# 3x3_Matrix.net
KiCad netlist of a schematic drawn in EAGLE
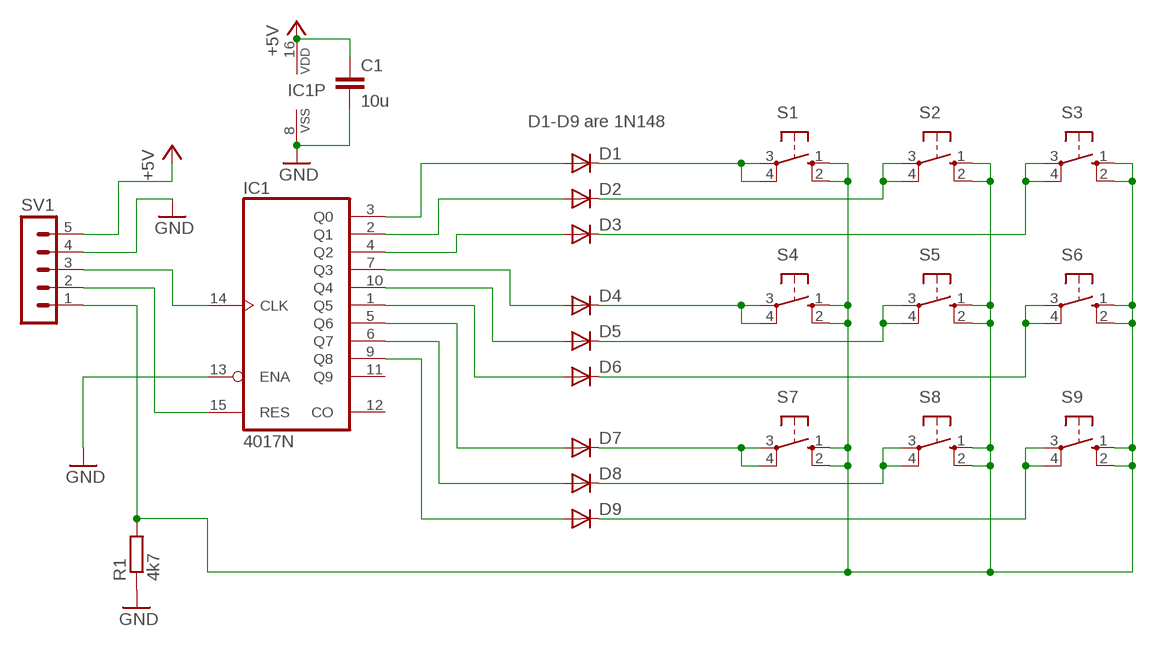
[diagram p0: schematic, sheet 1]

(export (version "E")
  (design (tool "Eeschema 10.0.6"))
  (components
    (comp (ref "C1")
      (value "10u")
      (footprint "eagle-import:C025-024X044")
      (libsource (lib "eagle-import") (part "C-EU025-024X044"))
    )
    (comp (ref "D1")
      (value "1N4148DO35-7")
      (footprint "eagle-import:DO35-7")
      (libsource (lib "eagle-import") (part "1N4148DO35-7"))
    )
    (comp (ref "D2")
      (value "1N4148DO35-7")
      (footprint "eagle-import:DO35-7")
      (libsource (lib "eagle-import") (part "1N4148DO35-7"))
    )
    (comp (ref "D3")
      (value "1N4148DO35-7")
      (footprint "eagle-import:DO35-7")
      (libsource (lib "eagle-import") (part "1N4148DO35-7"))
    )
    (comp (ref "D4")
      (value "1N4148DO35-7")
      (footprint "eagle-import:DO35-7")
      (libsource (lib "eagle-import") (part "1N4148DO35-7"))
    )
    (comp (ref "D5")
      (value "1N4148DO35-7")
      (footprint "eagle-import:DO35-7")
      (libsource (lib "eagle-import") (part "1N4148DO35-7"))
    )
    (comp (ref "D6")
      (value "1N4148DO35-7")
      (footprint "eagle-import:DO35-7")
      (libsource (lib "eagle-import") (part "1N4148DO35-7"))
    )
    (comp (ref "D7")
      (value "1N4148DO35-7")
      (footprint "eagle-import:DO35-7")
      (libsource (lib "eagle-import") (part "1N4148DO35-7"))
    )
    (comp (ref "D8")
      (value "1N4148DO35-7")
      (footprint "eagle-import:DO35-7")
      (libsource (lib "eagle-import") (part "1N4148DO35-7"))
    )
    (comp (ref "D9")
      (value "1N4148DO35-7")
      (footprint "eagle-import:DO35-7")
      (libsource (lib "eagle-import") (part "1N4148DO35-7"))
    )
    (comp (ref "IC1")
      (value "4017N")
      (footprint "eagle-import:DIL16")
      (libsource (lib "eagle-import") (part "4017N"))
    )
    (comp (ref "R1")
      (value "4k7")
      (footprint "eagle-import:0207_10")
      (libsource (lib "eagle-import") (part "R-EU_0207/10"))
    )
    (comp (ref "S1")
      (value "10-XX")
      (footprint "eagle-import:B3F-10XX")
      (fields (field (name "MPN") "B3F-1000"))
      (libsource (lib "eagle-import") (part "10-XX"))
    )
    (comp (ref "S2")
      (value "10-XX")
      (footprint "eagle-import:B3F-10XX")
      (fields (field (name "MPN") "B3F-1000"))
      (libsource (lib "eagle-import") (part "10-XX"))
    )
    (comp (ref "S3")
      (value "10-XX")
      (footprint "eagle-import:B3F-10XX")
      (fields (field (name "MPN") "B3F-1000"))
      (libsource (lib "eagle-import") (part "10-XX"))
    )
    (comp (ref "S4")
      (value "10-XX")
      (footprint "eagle-import:B3F-10XX")
      (fields (field (name "MPN") "B3F-1000"))
      (libsource (lib "eagle-import") (part "10-XX"))
    )
    (comp (ref "S5")
      (value "10-XX")
      (footprint "eagle-import:B3F-10XX")
      (fields (field (name "MPN") "B3F-1000"))
      (libsource (lib "eagle-import") (part "10-XX"))
    )
    (comp (ref "S6")
      (value "10-XX")
      (footprint "eagle-import:B3F-10XX")
      (fields (field (name "MPN") "B3F-1000"))
      (libsource (lib "eagle-import") (part "10-XX"))
    )
    (comp (ref "S7")
      (value "10-XX")
      (footprint "eagle-import:B3F-10XX")
      (fields (field (name "MPN") "B3F-1000"))
      (libsource (lib "eagle-import") (part "10-XX"))
    )
    (comp (ref "S8")
      (value "10-XX")
      (footprint "eagle-import:B3F-10XX")
      (fields (field (name "MPN") "B3F-1000"))
      (libsource (lib "eagle-import") (part "10-XX"))
    )
    (comp (ref "S9")
      (value "10-XX")
      (footprint "eagle-import:B3F-10XX")
      (fields (field (name "MPN") "B3F-1000"))
      (libsource (lib "eagle-import") (part "10-XX"))
    )
    (comp (ref "SV1")
      (value "MA05-1")
      (footprint "eagle-import:MA05-1")
      (libsource (lib "eagle-import") (part "MA05-1"))
    )
  )
  (nets
    (net (code "1") (name "+5V") (class "Default")
      (node (ref "C1") (pin "1") (pinfunction "1_1") (pintype "passive"))
      (node (ref "IC1") (pin "16") (pinfunction "VDD_16") (pintype "power_in"))
      (node (ref "SV1") (pin "5") (pinfunction "5_5") (pintype "passive"))
    )
    (net (code "2") (name "GND") (class "Default")
      (node (ref "C1") (pin "2") (pinfunction "2_2") (pintype "passive"))
      (node (ref "IC1") (pin "13") (pinfunction "ENA_13") (pintype "input"))
      (node (ref "IC1") (pin "8") (pinfunction "VSS_8") (pintype "power_in"))
      (node (ref "R1") (pin "1") (pinfunction "1_1") (pintype "passive"))
      (node (ref "SV1") (pin "4") (pinfunction "4_4") (pintype "passive"))
    )
    (net (code "3") (name "Net-(IC1A-CLK)") (class "Default")
      (node (ref "IC1") (pin "14") (pinfunction "CLK_14") (pintype "input"))
      (node (ref "SV1") (pin "3") (pinfunction "3_3") (pintype "passive"))
    )
    (net (code "4") (name "Net-(IC1A-Q0)") (class "Default")
      (node (ref "D1") (pin "A") (pinfunction "A_A") (pintype "passive"))
      (node (ref "IC1") (pin "3") (pinfunction "Q0_3") (pintype "output"))
    )
    (net (code "5") (name "Net-(IC1A-Q1)") (class "Default")
      (node (ref "D2") (pin "A") (pinfunction "A_A") (pintype "passive"))
      (node (ref "IC1") (pin "2") (pinfunction "Q1_2") (pintype "output"))
    )
    (net (code "6") (name "Net-(IC1A-Q2)") (class "Default")
      (node (ref "D3") (pin "A") (pinfunction "A_A") (pintype "passive"))
      (node (ref "IC1") (pin "4") (pinfunction "Q2_4") (pintype "output"))
    )
    (net (code "7") (name "Net-(IC1A-Q3)") (class "Default")
      (node (ref "D4") (pin "A") (pinfunction "A_A") (pintype "passive"))
      (node (ref "IC1") (pin "7") (pinfunction "Q3_7") (pintype "output"))
    )
    (net (code "8") (name "Net-(IC1A-Q4)") (class "Default")
      (node (ref "D5") (pin "A") (pinfunction "A_A") (pintype "passive"))
      (node (ref "IC1") (pin "10") (pinfunction "Q4_10") (pintype "output"))
    )
    (net (code "9") (name "Net-(IC1A-Q5)") (class "Default")
      (node (ref "D6") (pin "A") (pinfunction "A_A") (pintype "passive"))
      (node (ref "IC1") (pin "1") (pinfunction "Q5_1") (pintype "output"))
    )
    (net (code "10") (name "Net-(IC1A-Q6)") (class "Default")
      (node (ref "D7") (pin "A") (pinfunction "A_A") (pintype "passive"))
      (node (ref "IC1") (pin "5") (pinfunction "Q6_5") (pintype "output"))
    )
    (net (code "11") (name "Net-(IC1A-Q7)") (class "Default")
      (node (ref "D8") (pin "A") (pinfunction "A_A") (pintype "passive"))
      (node (ref "IC1") (pin "6") (pinfunction "Q7_6") (pintype "output"))
    )
    (net (code "12") (name "Net-(IC1A-Q8)") (class "Default")
      (node (ref "D9") (pin "A") (pinfunction "A_A") (pintype "passive"))
      (node (ref "IC1") (pin "9") (pinfunction "Q8_9") (pintype "output"))
    )
    (net (code "13") (name "Net-(IC1A-RES)") (class "Default")
      (node (ref "IC1") (pin "15") (pinfunction "RES_15") (pintype "input"))
      (node (ref "SV1") (pin "2") (pinfunction "2_2") (pintype "passive"))
    )
    (net (code "14") (name "Net-(S1-P)") (class "Default")
      (node (ref "D1") (pin "C") (pinfunction "C_C") (pintype "passive"))
      (node (ref "S1") (pin "3") (pinfunction "P_3") (pintype "passive"))
      (node (ref "S1") (pin "4") (pinfunction "P1_4") (pintype "passive"))
    )
    (net (code "15") (name "Net-(S1-S)") (class "Default")
      (node (ref "R1") (pin "2") (pinfunction "2_2") (pintype "passive"))
      (node (ref "S1") (pin "1") (pinfunction "S_1") (pintype "passive"))
      (node (ref "S1") (pin "2") (pinfunction "S1_2") (pintype "passive"))
      (node (ref "S2") (pin "1") (pinfunction "S_1") (pintype "passive"))
      (node (ref "S2") (pin "2") (pinfunction "S1_2") (pintype "passive"))
      (node (ref "S3") (pin "1") (pinfunction "S_1") (pintype "passive"))
      (node (ref "S3") (pin "2") (pinfunction "S1_2") (pintype "passive"))
      (node (ref "S4") (pin "1") (pinfunction "S_1") (pintype "passive"))
      (node (ref "S4") (pin "2") (pinfunction "S1_2") (pintype "passive"))
      (node (ref "S5") (pin "1") (pinfunction "S_1") (pintype "passive"))
      (node (ref "S5") (pin "2") (pinfunction "S1_2") (pintype "passive"))
      (node (ref "S6") (pin "1") (pinfunction "S_1") (pintype "passive"))
      (node (ref "S6") (pin "2") (pinfunction "S1_2") (pintype "passive"))
      (node (ref "S7") (pin "1") (pinfunction "S_1") (pintype "passive"))
      (node (ref "S7") (pin "2") (pinfunction "S1_2") (pintype "passive"))
      (node (ref "S8") (pin "1") (pinfunction "S_1") (pintype "passive"))
      (node (ref "S8") (pin "2") (pinfunction "S1_2") (pintype "passive"))
      (node (ref "S9") (pin "1") (pinfunction "S_1") (pintype "passive"))
      (node (ref "S9") (pin "2") (pinfunction "S1_2") (pintype "passive"))
      (node (ref "SV1") (pin "1") (pinfunction "1_1") (pintype "passive"))
    )
    (net (code "16") (name "Net-(S2-P)") (class "Default")
      (node (ref "D2") (pin "C") (pinfunction "C_C") (pintype "passive"))
      (node (ref "S2") (pin "3") (pinfunction "P_3") (pintype "passive"))
      (node (ref "S2") (pin "4") (pinfunction "P1_4") (pintype "passive"))
    )
    (net (code "17") (name "Net-(S3-P)") (class "Default")
      (node (ref "D3") (pin "C") (pinfunction "C_C") (pintype "passive"))
      (node (ref "S3") (pin "3") (pinfunction "P_3") (pintype "passive"))
      (node (ref "S3") (pin "4") (pinfunction "P1_4") (pintype "passive"))
    )
    (net (code "18") (name "Net-(S4-P)") (class "Default")
      (node (ref "D4") (pin "C") (pinfunction "C_C") (pintype "passive"))
      (node (ref "S4") (pin "3") (pinfunction "P_3") (pintype "passive"))
      (node (ref "S4") (pin "4") (pinfunction "P1_4") (pintype "passive"))
    )
    (net (code "19") (name "Net-(S5-P)") (class "Default")
      (node (ref "D5") (pin "C") (pinfunction "C_C") (pintype "passive"))
      (node (ref "S5") (pin "3") (pinfunction "P_3") (pintype "passive"))
      (node (ref "S5") (pin "4") (pinfunction "P1_4") (pintype "passive"))
    )
    (net (code "20") (name "Net-(S6-P)") (class "Default")
      (node (ref "D6") (pin "C") (pinfunction "C_C") (pintype "passive"))
      (node (ref "S6") (pin "3") (pinfunction "P_3") (pintype "passive"))
      (node (ref "S6") (pin "4") (pinfunction "P1_4") (pintype "passive"))
    )
    (net (code "21") (name "Net-(S7-P)") (class "Default")
      (node (ref "D7") (pin "C") (pinfunction "C_C") (pintype "passive"))
      (node (ref "S7") (pin "3") (pinfunction "P_3") (pintype "passive"))
      (node (ref "S7") (pin "4") (pinfunction "P1_4") (pintype "passive"))
    )
    (net (code "22") (name "Net-(S8-P)") (class "Default")
      (node (ref "D8") (pin "C") (pinfunction "C_C") (pintype "passive"))
      (node (ref "S8") (pin "3") (pinfunction "P_3") (pintype "passive"))
      (node (ref "S8") (pin "4") (pinfunction "P1_4") (pintype "passive"))
    )
    (net (code "23") (name "Net-(S9-P)") (class "Default")
      (node (ref "D9") (pin "C") (pinfunction "C_C") (pintype "passive"))
      (node (ref "S9") (pin "3") (pinfunction "P_3") (pintype "passive"))
      (node (ref "S9") (pin "4") (pinfunction "P1_4") (pintype "passive"))
    )
    (net (code "24") (name "unconnected-(IC1A-CO-Pad12)") (class "Default")
      (node (ref "IC1") (pin "12") (pinfunction "CO_12") (pintype "output"))
    )
    (net (code "25") (name "unconnected-(IC1A-Q9-Pad11)") (class "Default")
      (node (ref "IC1") (pin "11") (pinfunction "Q9_11") (pintype "output"))
    )
  )
)
